# Sheet1.net
KiCad netlist of a schematic drawn in Altium Designer
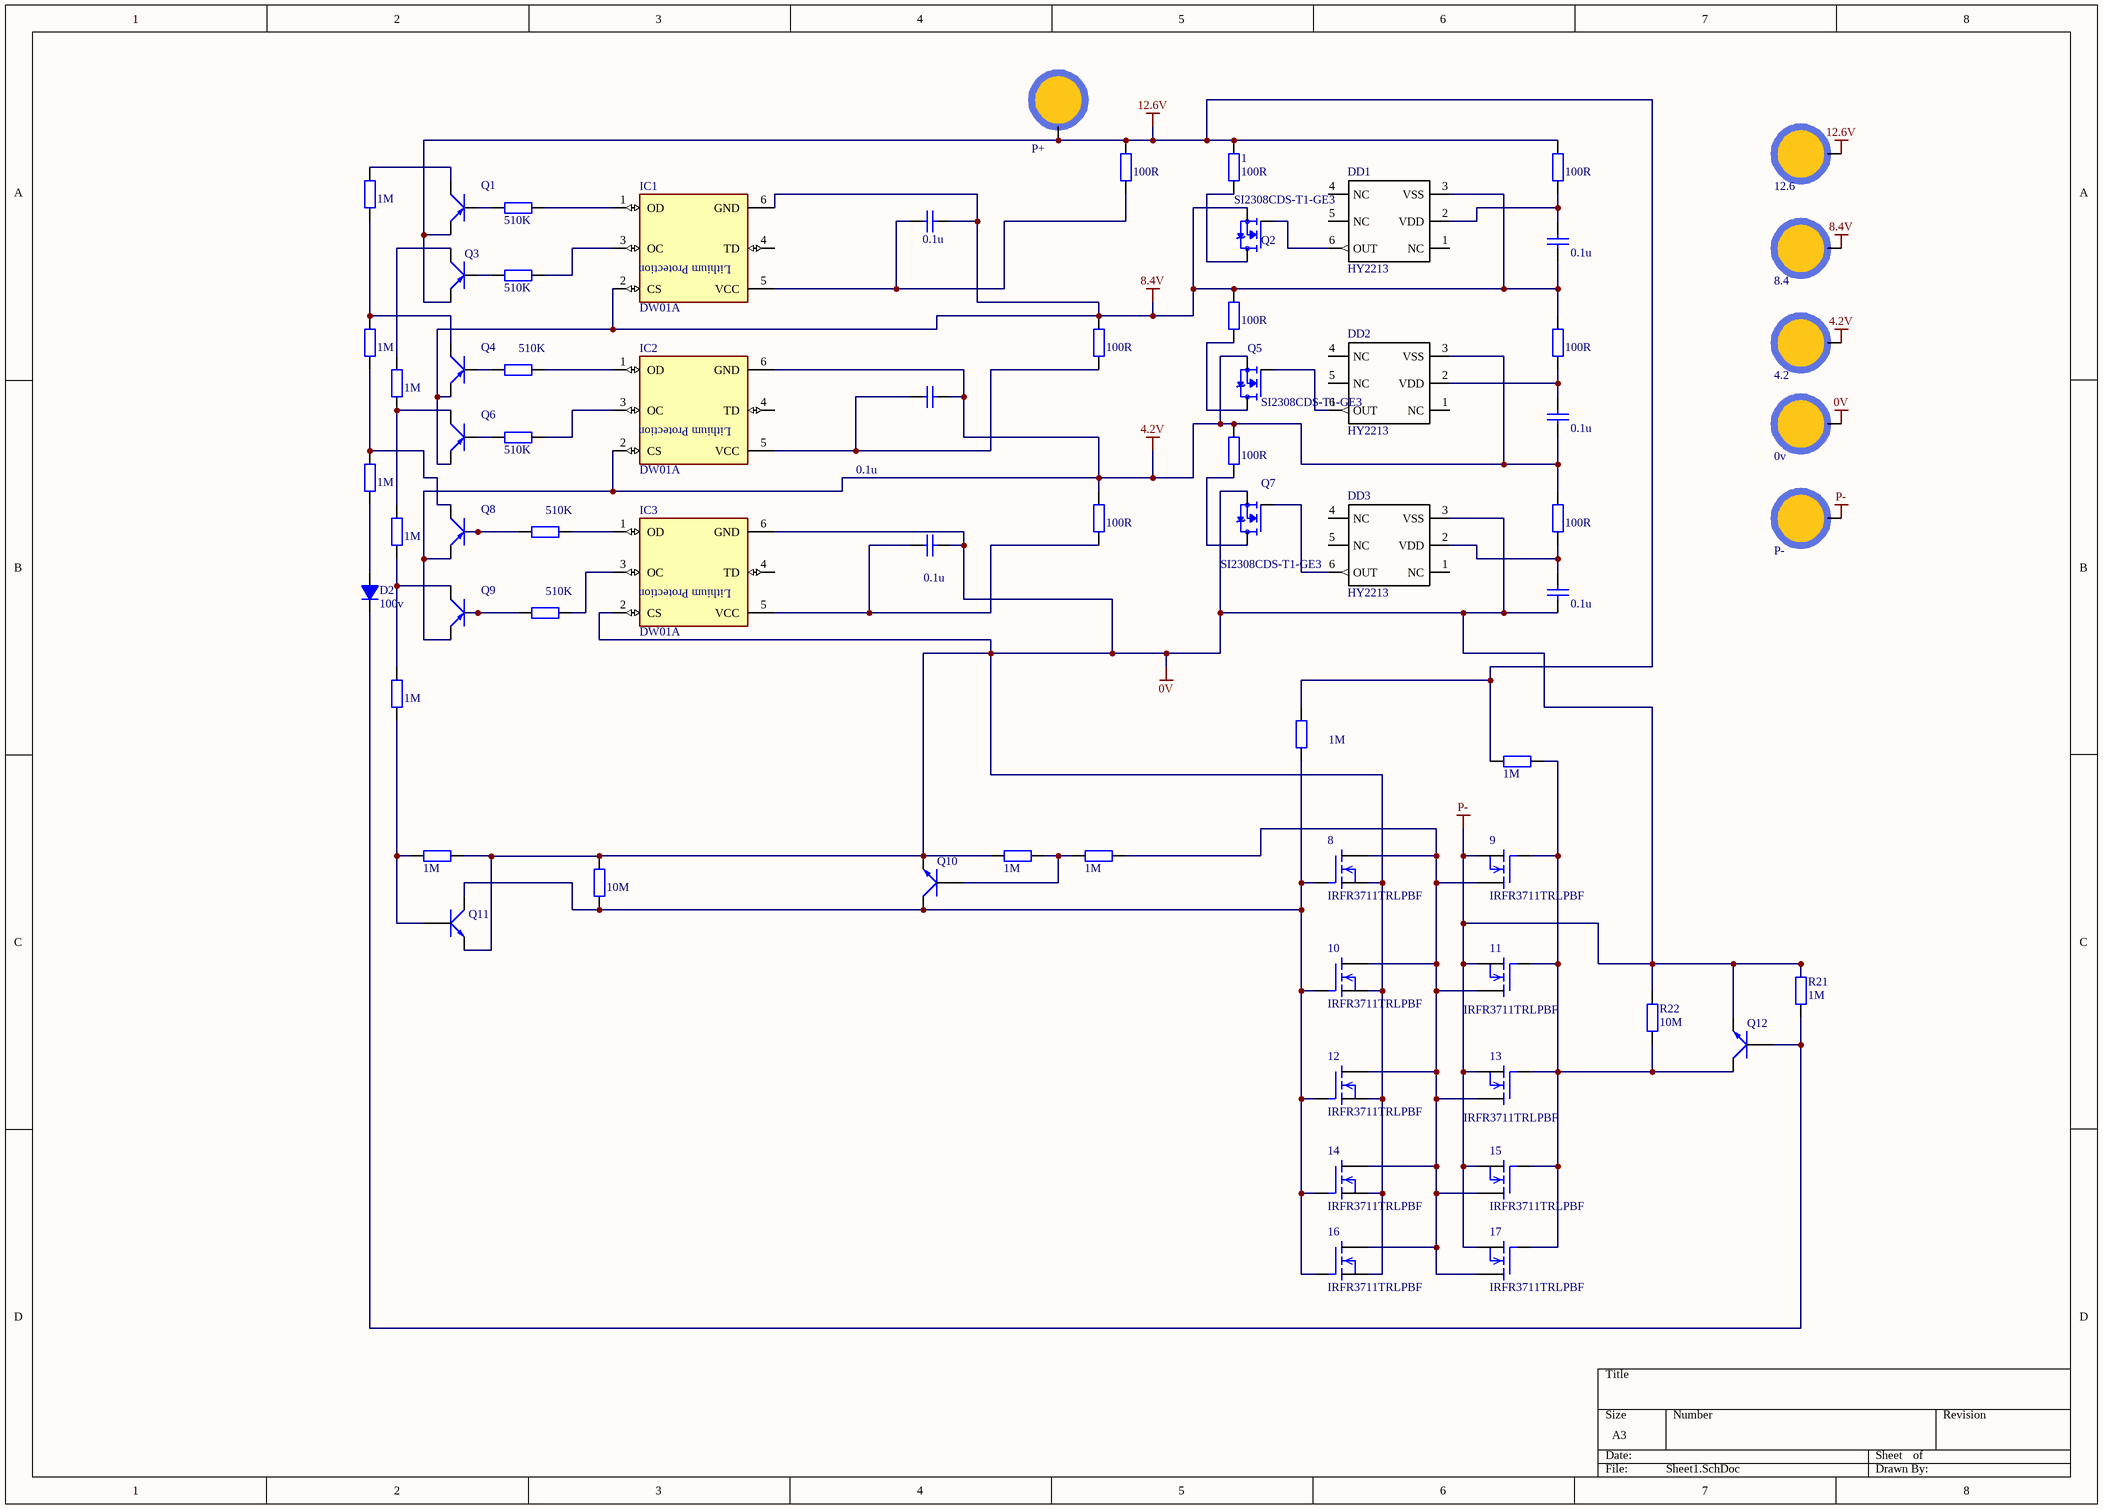
[diagram p0: Sheet1.SchDoc]

(export (version "E")
  (design (tool "Eeschema 10.0.6"))
  (components
    (comp (ref "0v")
      (value "DNP/MH")
      (footprint "SOMH1")
      (description "Solder Mounting, Hole 1mm")
      (libsource (lib "Library_TTT_CR") (part "SOMH1"))
    )
    (comp (ref "1")
      (value "100R")
      (footprint "tro smd 2512")
      (description "Dán")
      (libsource (lib "Altium_Lib_by_KhueNguyenCreator") (part "Tro 2512 5% 100R"))
    )
    (comp (ref "2")
      (value "1M")
      (footprint "tro smd 1206")
      (description "Dán")
      (libsource (lib "Altium_Lib_by_KhueNguyenCreator") (part "Tro 1206 1% 0.68R"))
    )
    (comp (ref "3")
      (value "100R")
      (footprint "tro smd 2512")
      (description "Dán")
      (libsource (lib "Altium_Lib_by_KhueNguyenCreator") (part "Tro 2512 5% 100R"))
    )
    (comp (ref "4")
      (value "1M")
      (footprint "tro smd 1206")
      (description "Dán")
      (libsource (lib "Altium_Lib_by_KhueNguyenCreator") (part "Tro 1206 1% 0.68R"))
    )
    (comp (ref "4.2")
      (value "DNP/MH")
      (footprint "SOMH1")
      (description "Solder Mounting, Hole 1mm")
      (libsource (lib "Library_TTT_CR") (part "SOMH1"))
    )
    (comp (ref "5")
      (value "1M")
      (footprint "tro smd 1206")
      (description "Dán")
      (libsource (lib "Altium_Lib_by_KhueNguyenCreator") (part "Tro 1206 1% 0.68R"))
    )
    (comp (ref "6")
      (value "100R")
      (footprint "tro smd 2512")
      (description "Dán")
      (libsource (lib "Altium_Lib_by_KhueNguyenCreator") (part "Tro 2512 5% 100R"))
    )
    (comp (ref "7")
      (value "1M")
      (footprint "tro smd 1206")
      (description "Dán")
      (libsource (lib "Altium_Lib_by_KhueNguyenCreator") (part "Tro 1206 1% 0.68R"))
    )
    (comp (ref "8")
      (value "IRFR3711TRLPBF")
      (footprint "TO252")
      (description "N-Channel 20V 100A _Tc_ 2.5W _Ta_, 120W _Tc_ Surface Mount D-Pak")
      (fields (field (name "MF") "Infineon"))
      (libsource (lib "IRFR3711TRLPBF") (part "IRFR3711TRLPBF"))
    )
    (comp (ref "8.4")
      (value "DNP/MH")
      (footprint "SOMH1")
      (description "Solder Mounting, Hole 1mm")
      (libsource (lib "Library_TTT_CR") (part "SOMH1"))
    )
    (comp (ref "9")
      (value "IRFR3711TRLPBF")
      (footprint "TO252")
      (description "N-Channel 20V 100A _Tc_ 2.5W _Ta_, 120W _Tc_ Surface Mount D-Pak")
      (fields (field (name "MF") "Infineon"))
      (libsource (lib "IRFR3711TRLPBF") (part "IRFR3711TRLPBF"))
    )
    (comp (ref "10")
      (value "IRFR3711TRLPBF")
      (footprint "TO252")
      (description "N-Channel 20V 100A _Tc_ 2.5W _Ta_, 120W _Tc_ Surface Mount D-Pak")
      (fields (field (name "MF") "Infineon"))
      (libsource (lib "IRFR3711TRLPBF") (part "IRFR3711TRLPBF"))
    )
    (comp (ref "11")
      (value "IRFR3711TRLPBF")
      (footprint "TO252")
      (description "N-Channel 20V 100A _Tc_ 2.5W _Ta_, 120W _Tc_ Surface Mount D-Pak")
      (fields (field (name "MF") "Infineon"))
      (libsource (lib "IRFR3711TRLPBF") (part "IRFR3711TRLPBF"))
    )
    (comp (ref "12")
      (value "IRFR3711TRLPBF")
      (footprint "TO252")
      (description "N-Channel 20V 100A _Tc_ 2.5W _Ta_, 120W _Tc_ Surface Mount D-Pak")
      (fields (field (name "MF") "Infineon"))
      (libsource (lib "IRFR3711TRLPBF") (part "IRFR3711TRLPBF"))
    )
    (comp (ref "12.6")
      (value "DNP/MH")
      (footprint "SOMH1")
      (description "Solder Mounting, Hole 1mm")
      (libsource (lib "Library_TTT_CR") (part "SOMH1"))
    )
    (comp (ref "13")
      (value "IRFR3711TRLPBF")
      (footprint "TO252")
      (description "N-Channel 20V 100A _Tc_ 2.5W _Ta_, 120W _Tc_ Surface Mount D-Pak")
      (fields (field (name "MF") "Infineon"))
      (libsource (lib "IRFR3711TRLPBF") (part "IRFR3711TRLPBF"))
    )
    (comp (ref "14")
      (value "IRFR3711TRLPBF")
      (footprint "TO252")
      (description "N-Channel 20V 100A _Tc_ 2.5W _Ta_, 120W _Tc_ Surface Mount D-Pak")
      (fields (field (name "MF") "Infineon"))
      (libsource (lib "IRFR3711TRLPBF") (part "IRFR3711TRLPBF"))
    )
    (comp (ref "15")
      (value "IRFR3711TRLPBF")
      (footprint "TO252")
      (description "N-Channel 20V 100A _Tc_ 2.5W _Ta_, 120W _Tc_ Surface Mount D-Pak")
      (fields (field (name "MF") "Infineon"))
      (libsource (lib "IRFR3711TRLPBF") (part "IRFR3711TRLPBF"))
    )
    (comp (ref "16")
      (value "IRFR3711TRLPBF")
      (footprint "TO252")
      (description "N-Channel 20V 100A _Tc_ 2.5W _Ta_, 120W _Tc_ Surface Mount D-Pak")
      (fields (field (name "MF") "Infineon"))
      (libsource (lib "IRFR3711TRLPBF") (part "IRFR3711TRLPBF"))
    )
    (comp (ref "17")
      (value "IRFR3711TRLPBF")
      (footprint "TO252")
      (description "N-Channel 20V 100A _Tc_ 2.5W _Ta_, 120W _Tc_ Surface Mount D-Pak")
      (fields (field (name "MF") "Infineon"))
      (libsource (lib "IRFR3711TRLPBF") (part "IRFR3711TRLPBF"))
    )
    (comp (ref "C1")
      (value "0.1u")
      (footprint "tu 1206")
      (description "Dán")
      (libsource (lib "Altium_Lib_by_KhueNguyenCreator") (part "Tu 1206 4.7nF 50V"))
    )
    (comp (ref "C2")
      (value "0.1u")
      (footprint "tu 1206")
      (description "Dán")
      (libsource (lib "Altium_Lib_by_KhueNguyenCreator") (part "Tu 1206 4.7nF 50V"))
    )
    (comp (ref "C3")
      (value "0.1u")
      (footprint "tu 1206")
      (description "Dán")
      (libsource (lib "Altium_Lib_by_KhueNguyenCreator") (part "Tu 1206 4.7nF 50V"))
    )
    (comp (ref "C4")
      (value "0.1u")
      (footprint "tu 1206")
      (description "Dán")
      (libsource (lib "Altium_Lib_by_KhueNguyenCreator") (part "Tu 1206 4.7nF 50V"))
    )
    (comp (ref "C5")
      (value "0.1u")
      (footprint "tu 1206")
      (description "Dán")
      (libsource (lib "Altium_Lib_by_KhueNguyenCreator") (part "Tu 1206 4.7nF 50V"))
    )
    (comp (ref "C6")
      (value "0.1u")
      (footprint "tu 1206")
      (description "Dán")
      (libsource (lib "Altium_Lib_by_KhueNguyenCreator") (part "Tu 1206 4.7nF 50V"))
    )
    (comp (ref "D2")
      (value "100v")
      (footprint "DIODE 0.5A")
      (description "Cắm")
      (libsource (lib "Altium_Lib_by_KhueNguyenCreator") (part "Diode 1N4148"))
    )
    (comp (ref "DD1")
      (value "HY2213")
      (footprint "SOT23-6")
      (description "1 Cell Li-ion/Polymer Battery Charge Balance IC")
      (libsource (lib "HY2213-BB3A") (part "HY2213"))
    )
    (comp (ref "DD2")
      (value "HY2213")
      (footprint "SOT23-6")
      (description "1 Cell Li-ion/Polymer Battery Charge Balance IC")
      (libsource (lib "HY2213-BB3A") (part "HY2213"))
    )
    (comp (ref "DD3")
      (value "HY2213")
      (footprint "SOT23-6")
      (description "1 Cell Li-ion/Polymer Battery Charge Balance IC")
      (libsource (lib "HY2213-BB3A") (part "HY2213"))
    )
    (comp (ref "IC1")
      (value "DW01A")
      (footprint "SOT23-6")
      (description "One Cell Lithium-ion/Polymer Battery Protection IC")
      (fields (field (name "MF") "Fortune Semiconductor"))
      (libsource (lib "DW01A") (part "DW01A"))
    )
    (comp (ref "IC2")
      (value "DW01A")
      (footprint "SOT23-6")
      (description "One Cell Lithium-ion/Polymer Battery Protection IC")
      (fields (field (name "MF") "Fortune Semiconductor"))
      (libsource (lib "DW01A") (part "DW01A"))
    )
    (comp (ref "IC3")
      (value "DW01A")
      (footprint "SOT23-6")
      (description "One Cell Lithium-ion/Polymer Battery Protection IC")
      (fields (field (name "MF") "Fortune Semiconductor"))
      (libsource (lib "DW01A") (part "DW01A"))
    )
    (comp (ref "P+")
      (value "DNP/MH")
      (footprint "SOMH1")
      (description "Solder Mounting, Hole 1mm")
      (libsource (lib "Library_TTT_CR") (part "SOMH1"))
    )
    (comp (ref "P-")
      (value "DNP/MH")
      (footprint "SOMH1")
      (description "Solder Mounting, Hole 1mm")
      (libsource (lib "Library_TTT_CR") (part "SOMH1"))
    )
    (comp (ref "Q1")
      (value "BA")
      (footprint "SOT23")
      (description "PNP 600mW, ECB")
      (libsource (lib "Altium_Lib_by_KhueNguyenCreator") (part "A1015 BA SMD"))
    )
    (comp (ref "Q2")
      (value "SI2308CDS-T1-GE3")
      (footprint "SOT95P237X112-3N")
      (description "N-Channel 60V 2.6A (Tc) 1.6W (Tc) Surface Mount SOT-23-3 (TO-236)")
      (fields (field (name "MF") "Vishay Siliconix"))
      (libsource (lib "SI2308CDS-T1-GE3") (part "SI2308CDS-T1-GE3"))
    )
    (comp (ref "Q3")
      (value "BA")
      (footprint "SOT23")
      (description "PNP 600mW, ECB")
      (libsource (lib "Altium_Lib_by_KhueNguyenCreator") (part "A1015 BA SMD"))
    )
    (comp (ref "Q4")
      (value "BA")
      (footprint "SOT23")
      (description "PNP 600mW, ECB")
      (libsource (lib "Altium_Lib_by_KhueNguyenCreator") (part "A1015 BA SMD"))
    )
    (comp (ref "Q5")
      (value "SI2308CDS-T1-GE3")
      (footprint "SOT95P237X112-3N")
      (description "N-Channel 60V 2.6A (Tc) 1.6W (Tc) Surface Mount SOT-23-3 (TO-236)")
      (fields (field (name "MF") "Vishay Siliconix"))
      (libsource (lib "SI2308CDS-T1-GE3") (part "SI2308CDS-T1-GE3"))
    )
    (comp (ref "Q6")
      (value "BA")
      (footprint "SOT23")
      (description "PNP 600mW, ECB")
      (libsource (lib "Altium_Lib_by_KhueNguyenCreator") (part "A1015 BA SMD"))
    )
    (comp (ref "Q7")
      (value "SI2308CDS-T1-GE3")
      (footprint "SOT95P237X112-3N")
      (description "N-Channel 60V 2.6A (Tc) 1.6W (Tc) Surface Mount SOT-23-3 (TO-236)")
      (fields (field (name "MF") "Vishay Siliconix"))
      (libsource (lib "SI2308CDS-T1-GE3") (part "SI2308CDS-T1-GE3"))
    )
    (comp (ref "Q8")
      (value "BA")
      (footprint "SOT23")
      (description "PNP 600mW, ECB")
      (libsource (lib "Altium_Lib_by_KhueNguyenCreator") (part "A1015 BA SMD"))
    )
    (comp (ref "Q9")
      (value "BA")
      (footprint "SOT23")
      (description "PNP 600mW, ECB")
      (libsource (lib "Altium_Lib_by_KhueNguyenCreator") (part "A1015 BA SMD"))
    )
    (comp (ref "Q10")
      (value "HF")
      (footprint "SOT23")
      (description "NPN transistor")
      (libsource (lib "Altium_Lib_by_KhueNguyenCreator") (part "C1815 HF SMD"))
    )
    (comp (ref "Q11")
      (value "HF")
      (footprint "SOT23")
      (description "NPN transistor")
      (libsource (lib "Altium_Lib_by_KhueNguyenCreator") (part "C1815 HF SMD"))
    )
    (comp (ref "Q12")
      (value "~")
      (footprint "SOT23")
      (description "NPN transistor")
      (libsource (lib "Altium_Lib_by_KhueNguyenCreator") (part "C1815 HF SMD"))
    )
    (comp (ref "R1")
      (value "100R")
      (footprint "tro smd 1206")
      (description "Dán")
      (libsource (lib "Altium_Lib_by_KhueNguyenCreator") (part "Tro 1206 1% 0.68R"))
    )
    (comp (ref "R2")
      (value "100R")
      (footprint "tro smd 1206")
      (description "Dán")
      (libsource (lib "Altium_Lib_by_KhueNguyenCreator") (part "Tro 1206 1% 0.68R"))
    )
    (comp (ref "R3")
      (value "510K")
      (footprint "tro smd 1206")
      (description "Dán")
      (libsource (lib "Altium_Lib_by_KhueNguyenCreator") (part "Tro 1206 1% 0.68R"))
    )
    (comp (ref "R4")
      (value "510K")
      (footprint "tro smd 1206")
      (description "Dán")
      (libsource (lib "Altium_Lib_by_KhueNguyenCreator") (part "Tro 1206 1% 0.68R"))
    )
    (comp (ref "R5")
      (value "510K")
      (footprint "tro smd 1206")
      (description "Dán")
      (libsource (lib "Altium_Lib_by_KhueNguyenCreator") (part "Tro 1206 1% 0.68R"))
    )
    (comp (ref "R6")
      (value "100R")
      (footprint "tro smd 1206")
      (description "Dán")
      (libsource (lib "Altium_Lib_by_KhueNguyenCreator") (part "Tro 1206 1% 0.68R"))
    )
    (comp (ref "R7")
      (value "100R")
      (footprint "tro smd 1206")
      (description "Dán")
      (libsource (lib "Altium_Lib_by_KhueNguyenCreator") (part "Tro 1206 1% 0.68R"))
    )
    (comp (ref "R8")
      (value "510K")
      (footprint "tro smd 1206")
      (description "Dán")
      (libsource (lib "Altium_Lib_by_KhueNguyenCreator") (part "Tro 1206 1% 0.68R"))
    )
    (comp (ref "R9")
      (value "510K")
      (footprint "tro smd 1206")
      (description "Dán")
      (libsource (lib "Altium_Lib_by_KhueNguyenCreator") (part "Tro 1206 1% 0.68R"))
    )
    (comp (ref "R10")
      (value "100R")
      (footprint "tro smd 1206")
      (description "Dán")
      (libsource (lib "Altium_Lib_by_KhueNguyenCreator") (part "Tro 1206 1% 0.68R"))
    )
    (comp (ref "R11")
      (value "100R")
      (footprint "tro smd 1206")
      (description "Dán")
      (libsource (lib "Altium_Lib_by_KhueNguyenCreator") (part "Tro 1206 1% 0.68R"))
    )
    (comp (ref "R12")
      (value "1M")
      (footprint "tro smd 1206")
      (description "Dán")
      (libsource (lib "Altium_Lib_by_KhueNguyenCreator") (part "Tro 1206 1% 0.68R"))
    )
    (comp (ref "R13")
      (value "510K")
      (footprint "tro smd 1206")
      (description "Dán")
      (libsource (lib "Altium_Lib_by_KhueNguyenCreator") (part "Tro 1206 1% 0.68R"))
    )
    (comp (ref "R14")
      (value "1M")
      (footprint "tro smd 1206")
      (description "Dán")
      (libsource (lib "Altium_Lib_by_KhueNguyenCreator") (part "Tro 1206 1% 0.68R"))
    )
    (comp (ref "R15")
      (value "1M")
      (footprint "tro smd 1206")
      (description "Dán")
      (libsource (lib "Altium_Lib_by_KhueNguyenCreator") (part "Tro 1206 1% 0.68R"))
    )
    (comp (ref "R16")
      (value "1M")
      (footprint "tro smd 1206")
      (description "Dán")
      (libsource (lib "Altium_Lib_by_KhueNguyenCreator") (part "Tro 1206 1% 0.68R"))
    )
    (comp (ref "R17")
      (value "1M")
      (footprint "tro smd 1206")
      (description "Dán")
      (libsource (lib "Altium_Lib_by_KhueNguyenCreator") (part "Tro 1206 1% 0.68R"))
    )
    (comp (ref "R18")
      (value "1M")
      (footprint "tro smd 1206")
      (description "Dán")
      (libsource (lib "Altium_Lib_by_KhueNguyenCreator") (part "Tro 1206 1% 0.68R"))
    )
    (comp (ref "R19")
      (value "1M")
      (footprint "tro smd 1206")
      (description "Dán")
      (libsource (lib "Altium_Lib_by_KhueNguyenCreator") (part "Tro 1206 1% 0.68R"))
    )
    (comp (ref "R20")
      (value "10M")
      (footprint "tro smd 1206")
      (description "Dán")
      (libsource (lib "Altium_Lib_by_KhueNguyenCreator") (part "Tro 1206 1% 0.68R"))
    )
    (comp (ref "R21")
      (value "1M")
      (footprint "tro smd 1206")
      (description "Dán")
      (libsource (lib "Altium_Lib_by_KhueNguyenCreator") (part "Tro 1206 1% 0.68R"))
    )
    (comp (ref "R22")
      (value "10M")
      (footprint "tro smd 1206")
      (description "Dán")
      (libsource (lib "Altium_Lib_by_KhueNguyenCreator") (part "Tro 1206 1% 0.68R"))
    )
  )
  (nets
    (net (code "1") (name "0V") (class "Default")
      (node (ref "0v") (pin "1") (pinfunction "1_1") (pintype "bidirectional"))
      (node (ref "10") (pin "3") (pinfunction "S_3") (pintype "passive"))
      (node (ref "11") (pin "3") (pinfunction "S_3") (pintype "passive"))
      (node (ref "12") (pin "3") (pinfunction "S_3") (pintype "passive"))
      (node (ref "13") (pin "3") (pinfunction "S_3") (pintype "passive"))
      (node (ref "14") (pin "3") (pinfunction "S_3") (pintype "passive"))
      (node (ref "15") (pin "3") (pinfunction "S_3") (pintype "passive"))
      (node (ref "16") (pin "3") (pinfunction "S_3") (pintype "passive"))
      (node (ref "17") (pin "3") (pinfunction "S_3") (pintype "passive"))
      (node (ref "8") (pin "3") (pinfunction "S_3") (pintype "passive"))
      (node (ref "9") (pin "3") (pinfunction "S_3") (pintype "passive"))
      (node (ref "C5") (pin "1") (pinfunction "1_1") (pintype "passive"))
      (node (ref "C6") (pin "2") (pinfunction "2_2") (pintype "passive"))
      (node (ref "DD3") (pin "3") (pinfunction "VSS_3") (pintype "power_in"))
      (node (ref "IC3") (pin "2") (pinfunction "CS_2") (pintype "bidirectional"))
      (node (ref "IC3") (pin "6") (pinfunction "GND_6") (pintype "power_in"))
      (node (ref "P-") (pin "1") (pinfunction "1_1") (pintype "bidirectional"))
      (node (ref "Q10") (pin "2") (pinfunction "E_2") (pintype "passive"))
      (node (ref "Q11") (pin "2") (pinfunction "E_2") (pintype "passive"))
      (node (ref "Q12") (pin "2") (pinfunction "E_2") (pintype "passive"))
      (node (ref "Q7") (pin "2") (pinfunction "S_2") (pintype "passive"))
      (node (ref "R17") (pin "1") (pinfunction "1_1") (pintype "passive"))
      (node (ref "R18") (pin "2") (pinfunction "2_2") (pintype "passive"))
      (node (ref "R20") (pin "1") (pinfunction "1_1") (pintype "passive"))
      (node (ref "R21") (pin "2") (pinfunction "2_2") (pintype "passive"))
      (node (ref "R22") (pin "1") (pinfunction "1_1") (pintype "passive"))
    )
    (net (code "2") (name "4.2V") (class "Default")
      (node (ref "4.2") (pin "1") (pinfunction "1_1") (pintype "bidirectional"))
      (node (ref "6") (pin "2") (pinfunction "2_2") (pintype "passive"))
      (node (ref "C3") (pin "1") (pinfunction "1_1") (pintype "passive"))
      (node (ref "C4") (pin "2") (pinfunction "2_2") (pintype "passive"))
      (node (ref "DD2") (pin "3") (pinfunction "VSS_3") (pintype "power_in"))
      (node (ref "IC2") (pin "2") (pinfunction "CS_2") (pintype "bidirectional"))
      (node (ref "IC2") (pin "6") (pinfunction "GND_6") (pintype "power_in"))
      (node (ref "Q5") (pin "2") (pinfunction "S_2") (pintype "passive"))
      (node (ref "Q8") (pin "2") (pinfunction "E_2") (pintype "passive"))
      (node (ref "Q9") (pin "2") (pinfunction "E_2") (pintype "passive"))
      (node (ref "R10") (pin "2") (pinfunction "2_2") (pintype "passive"))
      (node (ref "R11") (pin "1") (pinfunction "1_1") (pintype "passive"))
    )
    (net (code "3") (name "8.4V") (class "Default")
      (node (ref "3") (pin "2") (pinfunction "2_2") (pintype "passive"))
      (node (ref "8.4") (pin "1") (pinfunction "1_1") (pintype "bidirectional"))
      (node (ref "C1") (pin "1") (pinfunction "1_1") (pintype "passive"))
      (node (ref "C2") (pin "2") (pinfunction "2_2") (pintype "passive"))
      (node (ref "DD1") (pin "3") (pinfunction "VSS_3") (pintype "power_in"))
      (node (ref "IC1") (pin "2") (pinfunction "CS_2") (pintype "bidirectional"))
      (node (ref "IC1") (pin "6") (pinfunction "GND_6") (pintype "power_in"))
      (node (ref "Q2") (pin "2") (pinfunction "S_2") (pintype "passive"))
      (node (ref "Q4") (pin "2") (pinfunction "E_2") (pintype "passive"))
      (node (ref "Q6") (pin "2") (pinfunction "E_2") (pintype "passive"))
      (node (ref "R6") (pin "1") (pinfunction "1_1") (pintype "passive"))
      (node (ref "R7") (pin "1") (pinfunction "1_1") (pintype "passive"))
    )
    (net (code "4") (name "12.6V") (class "Default")
      (node (ref "1") (pin "2") (pinfunction "2_2") (pintype "passive"))
      (node (ref "12.6") (pin "1") (pinfunction "1_1") (pintype "bidirectional"))
      (node (ref "P+") (pin "1") (pinfunction "1_1") (pintype "bidirectional"))
      (node (ref "Q1") (pin "2") (pinfunction "E_2") (pintype "passive"))
      (node (ref "Q3") (pin "2") (pinfunction "E_2") (pintype "passive"))
      (node (ref "R1") (pin "1") (pinfunction "1_1") (pintype "passive"))
      (node (ref "R15") (pin "1") (pinfunction "1_1") (pintype "passive"))
      (node (ref "R16") (pin "1") (pinfunction "1_1") (pintype "passive"))
      (node (ref "R2") (pin "1") (pinfunction "1_1") (pintype "passive"))
    )
    (net (code "5") (name "Net-(10-D)") (class "Default")
      (node (ref "10") (pin "2") (pinfunction "D_2") (pintype "passive"))
      (node (ref "11") (pin "2") (pinfunction "D_2") (pintype "passive"))
      (node (ref "12") (pin "2") (pinfunction "D_2") (pintype "passive"))
      (node (ref "13") (pin "2") (pinfunction "D_2") (pintype "passive"))
      (node (ref "14") (pin "2") (pinfunction "D_2") (pintype "passive"))
      (node (ref "15") (pin "2") (pinfunction "D_2") (pintype "passive"))
      (node (ref "16") (pin "2") (pinfunction "D_2") (pintype "passive"))
      (node (ref "17") (pin "2") (pinfunction "D_2") (pintype "passive"))
      (node (ref "8") (pin "2") (pinfunction "D_2") (pintype "passive"))
      (node (ref "9") (pin "2") (pinfunction "D_2") (pintype "passive"))
      (node (ref "R19") (pin "1") (pinfunction "1_1") (pintype "passive"))
    )
    (net (code "6") (name "Net-(10-G)") (class "Default")
      (node (ref "10") (pin "1") (pinfunction "G_1") (pintype "passive"))
      (node (ref "12") (pin "1") (pinfunction "G_1") (pintype "passive"))
      (node (ref "14") (pin "1") (pinfunction "G_1") (pintype "passive"))
      (node (ref "16") (pin "1") (pinfunction "G_1") (pintype "passive"))
      (node (ref "8") (pin "1") (pinfunction "G_1") (pintype "passive"))
      (node (ref "Q10") (pin "3") (pinfunction "C_3") (pintype "passive"))
      (node (ref "Q11") (pin "3") (pinfunction "C_3") (pintype "passive"))
      (node (ref "R15") (pin "2") (pinfunction "2_2") (pintype "passive"))
      (node (ref "R20") (pin "2") (pinfunction "2_2") (pintype "passive"))
    )
    (net (code "7") (name "Net-(11-G)") (class "Default")
      (node (ref "11") (pin "1") (pinfunction "G_1") (pintype "passive"))
      (node (ref "13") (pin "1") (pinfunction "G_1") (pintype "passive"))
      (node (ref "15") (pin "1") (pinfunction "G_1") (pintype "passive"))
      (node (ref "17") (pin "1") (pinfunction "G_1") (pintype "passive"))
      (node (ref "9") (pin "1") (pinfunction "G_1") (pintype "passive"))
      (node (ref "Q12") (pin "3") (pinfunction "C_3") (pintype "passive"))
      (node (ref "R16") (pin "2") (pinfunction "2_2") (pintype "passive"))
      (node (ref "R22") (pin "2") (pinfunction "2_2") (pintype "passive"))
    )
    (net (code "8") (name "Net-(D2-A)") (class "Default")
      (node (ref "7") (pin "1") (pinfunction "1_1") (pintype "passive"))
      (node (ref "D2") (pin "1") (pinfunction "A_1") (pintype "passive"))
    )
    (net (code "9") (name "Net-(D2-K)") (class "Default")
      (node (ref "D2") (pin "2") (pinfunction "K_2") (pintype "passive"))
      (node (ref "Q12") (pin "1") (pinfunction "B_1") (pintype "passive"))
      (node (ref "R21") (pin "1") (pinfunction "1_1") (pintype "passive"))
    )
    (net (code "10") (name "Net-(DD1-OUT)") (class "Default")
      (node (ref "DD1") (pin "6") (pinfunction "OUT_6") (pintype "output"))
      (node (ref "Q2") (pin "1") (pinfunction "G_1") (pintype "passive"))
    )
    (net (code "11") (name "Net-(DD1-VDD)") (class "Default")
      (node (ref "C2") (pin "1") (pinfunction "1_1") (pintype "passive"))
      (node (ref "DD1") (pin "2") (pinfunction "VDD_2") (pintype "power_in"))
      (node (ref "R2") (pin "2") (pinfunction "2_2") (pintype "passive"))
    )
    (net (code "12") (name "Net-(DD2-OUT)") (class "Default")
      (node (ref "DD2") (pin "6") (pinfunction "OUT_6") (pintype "output"))
      (node (ref "Q5") (pin "1") (pinfunction "G_1") (pintype "passive"))
    )
    (net (code "13") (name "Net-(DD2-VDD)") (class "Default")
      (node (ref "C4") (pin "1") (pinfunction "1_1") (pintype "passive"))
      (node (ref "DD2") (pin "2") (pinfunction "VDD_2") (pintype "power_in"))
      (node (ref "R7") (pin "2") (pinfunction "2_2") (pintype "passive"))
    )
    (net (code "14") (name "Net-(DD3-OUT)") (class "Default")
      (node (ref "DD3") (pin "6") (pinfunction "OUT_6") (pintype "output"))
      (node (ref "Q7") (pin "1") (pinfunction "G_1") (pintype "passive"))
    )
    (net (code "15") (name "Net-(DD3-VDD)") (class "Default")
      (node (ref "C6") (pin "1") (pinfunction "1_1") (pintype "passive"))
      (node (ref "DD3") (pin "2") (pinfunction "VDD_2") (pintype "power_in"))
      (node (ref "R11") (pin "2") (pinfunction "2_2") (pintype "passive"))
    )
    (net (code "16") (name "Net-(IC1-OC)") (class "Default")
      (node (ref "IC1") (pin "3") (pinfunction "OC_3") (pintype "bidirectional"))
      (node (ref "R4") (pin "2") (pinfunction "2_2") (pintype "passive"))
    )
    (net (code "17") (name "Net-(IC1-OD)") (class "Default")
      (node (ref "IC1") (pin "1") (pinfunction "OD_1") (pintype "bidirectional"))
      (node (ref "R3") (pin "2") (pinfunction "2_2") (pintype "passive"))
    )
    (net (code "18") (name "Net-(IC1-VCC)") (class "Default")
      (node (ref "C1") (pin "2") (pinfunction "2_2") (pintype "passive"))
      (node (ref "IC1") (pin "5") (pinfunction "VCC_5") (pintype "power_in"))
      (node (ref "R1") (pin "2") (pinfunction "2_2") (pintype "passive"))
    )
    (net (code "19") (name "Net-(IC2-OC)") (class "Default")
      (node (ref "IC2") (pin "3") (pinfunction "OC_3") (pintype "bidirectional"))
      (node (ref "R8") (pin "1") (pinfunction "1_1") (pintype "passive"))
    )
    (net (code "20") (name "Net-(IC2-OD)") (class "Default")
      (node (ref "IC2") (pin "1") (pinfunction "OD_1") (pintype "bidirectional"))
      (node (ref "R5") (pin "1") (pinfunction "1_1") (pintype "passive"))
    )
    (net (code "21") (name "Net-(IC2-VCC)") (class "Default")
      (node (ref "C3") (pin "2") (pinfunction "2_2") (pintype "passive"))
      (node (ref "IC2") (pin "5") (pinfunction "VCC_5") (pintype "power_in"))
      (node (ref "R6") (pin "2") (pinfunction "2_2") (pintype "passive"))
    )
    (net (code "22") (name "Net-(IC3-OC)") (class "Default")
      (node (ref "IC3") (pin "3") (pinfunction "OC_3") (pintype "bidirectional"))
      (node (ref "R13") (pin "1") (pinfunction "1_1") (pintype "passive"))
    )
    (net (code "23") (name "Net-(IC3-OD)") (class "Default")
      (node (ref "IC3") (pin "1") (pinfunction "OD_1") (pintype "bidirectional"))
      (node (ref "R9") (pin "1") (pinfunction "1_1") (pintype "passive"))
    )
    (net (code "24") (name "Net-(IC3-VCC)") (class "Default")
      (node (ref "C5") (pin "2") (pinfunction "2_2") (pintype "passive"))
      (node (ref "IC3") (pin "5") (pinfunction "VCC_5") (pintype "power_in"))
      (node (ref "R10") (pin "1") (pinfunction "1_1") (pintype "passive"))
    )
    (net (code "25") (name "Net-(Q1-B)") (class "Default")
      (node (ref "Q1") (pin "1") (pinfunction "B_1") (pintype "passive"))
      (node (ref "R3") (pin "1") (pinfunction "1_1") (pintype "passive"))
    )
    (net (code "26") (name "Net-(Q1-C)") (class "Default")
      (node (ref "2") (pin "2") (pinfunction "2_2") (pintype "passive"))
      (node (ref "Q1") (pin "3") (pinfunction "C_3") (pintype "passive"))
    )
    (net (code "27") (name "Net-(Q2-D)") (class "Default")
      (node (ref "1") (pin "1") (pinfunction "1_1") (pintype "passive"))
      (node (ref "Q2") (pin "3") (pinfunction "D_3") (pintype "passive"))
    )
    (net (code "28") (name "Net-(Q3-B)") (class "Default")
      (node (ref "Q3") (pin "1") (pinfunction "B_1") (pintype "passive"))
      (node (ref "R4") (pin "1") (pinfunction "1_1") (pintype "passive"))
    )
    (net (code "29") (name "Net-(Q3-C)") (class "Default")
      (node (ref "5") (pin "2") (pinfunction "2_2") (pintype "passive"))
      (node (ref "Q3") (pin "3") (pinfunction "C_3") (pintype "passive"))
    )
    (net (code "30") (name "Net-(Q4-B)") (class "Default")
      (node (ref "Q4") (pin "1") (pinfunction "B_1") (pintype "passive"))
      (node (ref "R5") (pin "2") (pinfunction "2_2") (pintype "passive"))
    )
    (net (code "31") (name "Net-(Q4-C)") (class "Default")
      (node (ref "2") (pin "1") (pinfunction "1_1") (pintype "passive"))
      (node (ref "4") (pin "2") (pinfunction "2_2") (pintype "passive"))
      (node (ref "Q4") (pin "3") (pinfunction "C_3") (pintype "passive"))
    )
    (net (code "32") (name "Net-(Q5-D)") (class "Default")
      (node (ref "3") (pin "1") (pinfunction "1_1") (pintype "passive"))
      (node (ref "Q5") (pin "3") (pinfunction "D_3") (pintype "passive"))
    )
    (net (code "33") (name "Net-(Q6-B)") (class "Default")
      (node (ref "Q6") (pin "1") (pinfunction "B_1") (pintype "passive"))
      (node (ref "R8") (pin "2") (pinfunction "2_2") (pintype "passive"))
    )
    (net (code "34") (name "Net-(Q6-C)") (class "Default")
      (node (ref "5") (pin "1") (pinfunction "1_1") (pintype "passive"))
      (node (ref "Q6") (pin "3") (pinfunction "C_3") (pintype "passive"))
      (node (ref "R12") (pin "2") (pinfunction "2_2") (pintype "passive"))
    )
    (net (code "35") (name "Net-(Q7-D)") (class "Default")
      (node (ref "6") (pin "1") (pinfunction "1_1") (pintype "passive"))
      (node (ref "Q7") (pin "3") (pinfunction "D_3") (pintype "passive"))
    )
    (net (code "36") (name "Net-(Q8-B)") (class "Default")
      (node (ref "Q8") (pin "1") (pinfunction "B_1") (pintype "passive"))
      (node (ref "R9") (pin "2") (pinfunction "2_2") (pintype "passive"))
    )
    (net (code "37") (name "Net-(Q8-C)") (class "Default")
      (node (ref "4") (pin "1") (pinfunction "1_1") (pintype "passive"))
      (node (ref "7") (pin "2") (pinfunction "2_2") (pintype "passive"))
      (node (ref "Q8") (pin "3") (pinfunction "C_3") (pintype "passive"))
    )
    (net (code "38") (name "Net-(Q9-B)") (class "Default")
      (node (ref "Q9") (pin "1") (pinfunction "B_1") (pintype "passive"))
      (node (ref "R13") (pin "2") (pinfunction "2_2") (pintype "passive"))
    )
    (net (code "39") (name "Net-(Q9-C)") (class "Default")
      (node (ref "Q9") (pin "3") (pinfunction "C_3") (pintype "passive"))
      (node (ref "R12") (pin "1") (pinfunction "1_1") (pintype "passive"))
      (node (ref "R14") (pin "2") (pinfunction "2_2") (pintype "passive"))
    )
    (net (code "40") (name "Net-(Q10-B)") (class "Default")
      (node (ref "Q10") (pin "1") (pinfunction "B_1") (pintype "passive"))
      (node (ref "R18") (pin "1") (pinfunction "1_1") (pintype "passive"))
      (node (ref "R19") (pin "2") (pinfunction "2_2") (pintype "passive"))
    )
    (net (code "41") (name "Net-(Q11-B)") (class "Default")
      (node (ref "Q11") (pin "1") (pinfunction "B_1") (pintype "passive"))
      (node (ref "R14") (pin "1") (pinfunction "1_1") (pintype "passive"))
      (node (ref "R17") (pin "2") (pinfunction "2_2") (pintype "passive"))
    )
    (net (code "42") (name "unconnected-(DD1-NC-Pad1)") (class "Default")
      (node (ref "DD1") (pin "1") (pinfunction "NC_1") (pintype "tri_state"))
    )
    (net (code "43") (name "unconnected-(DD1-NC-Pad4)") (class "Default")
      (node (ref "DD1") (pin "4") (pinfunction "NC_4") (pintype "tri_state"))
    )
    (net (code "44") (name "unconnected-(DD1-NC-Pad5)") (class "Default")
      (node (ref "DD1") (pin "5") (pinfunction "NC_5") (pintype "tri_state"))
    )
    (net (code "45") (name "unconnected-(DD2-NC-Pad1)") (class "Default")
      (node (ref "DD2") (pin "1") (pinfunction "NC_1") (pintype "tri_state"))
    )
    (net (code "46") (name "unconnected-(DD2-NC-Pad4)") (class "Default")
      (node (ref "DD2") (pin "4") (pinfunction "NC_4") (pintype "tri_state"))
    )
    (net (code "47") (name "unconnected-(DD2-NC-Pad5)") (class "Default")
      (node (ref "DD2") (pin "5") (pinfunction "NC_5") (pintype "tri_state"))
    )
    (net (code "48") (name "unconnected-(DD3-NC-Pad1)") (class "Default")
      (node (ref "DD3") (pin "1") (pinfunction "NC_1") (pintype "tri_state"))
    )
    (net (code "49") (name "unconnected-(DD3-NC-Pad4)") (class "Default")
      (node (ref "DD3") (pin "4") (pinfunction "NC_4") (pintype "tri_state"))
    )
    (net (code "50") (name "unconnected-(DD3-NC-Pad5)") (class "Default")
      (node (ref "DD3") (pin "5") (pinfunction "NC_5") (pintype "tri_state"))
    )
    (net (code "51") (name "unconnected-(IC1-TD-Pad4)") (class "Default")
      (node (ref "IC1") (pin "4") (pinfunction "TD_4") (pintype "bidirectional"))
    )
    (net (code "52") (name "unconnected-(IC2-TD-Pad4)") (class "Default")
      (node (ref "IC2") (pin "4") (pinfunction "TD_4") (pintype "bidirectional"))
    )
    (net (code "53") (name "unconnected-(IC3-TD-Pad4)") (class "Default")
      (node (ref "IC3") (pin "4") (pinfunction "TD_4") (pintype "bidirectional"))
    )
  )
)
